# VALVEBOARD_Controller.net
KiCad netlist of a schematic drawn in Altium Designer
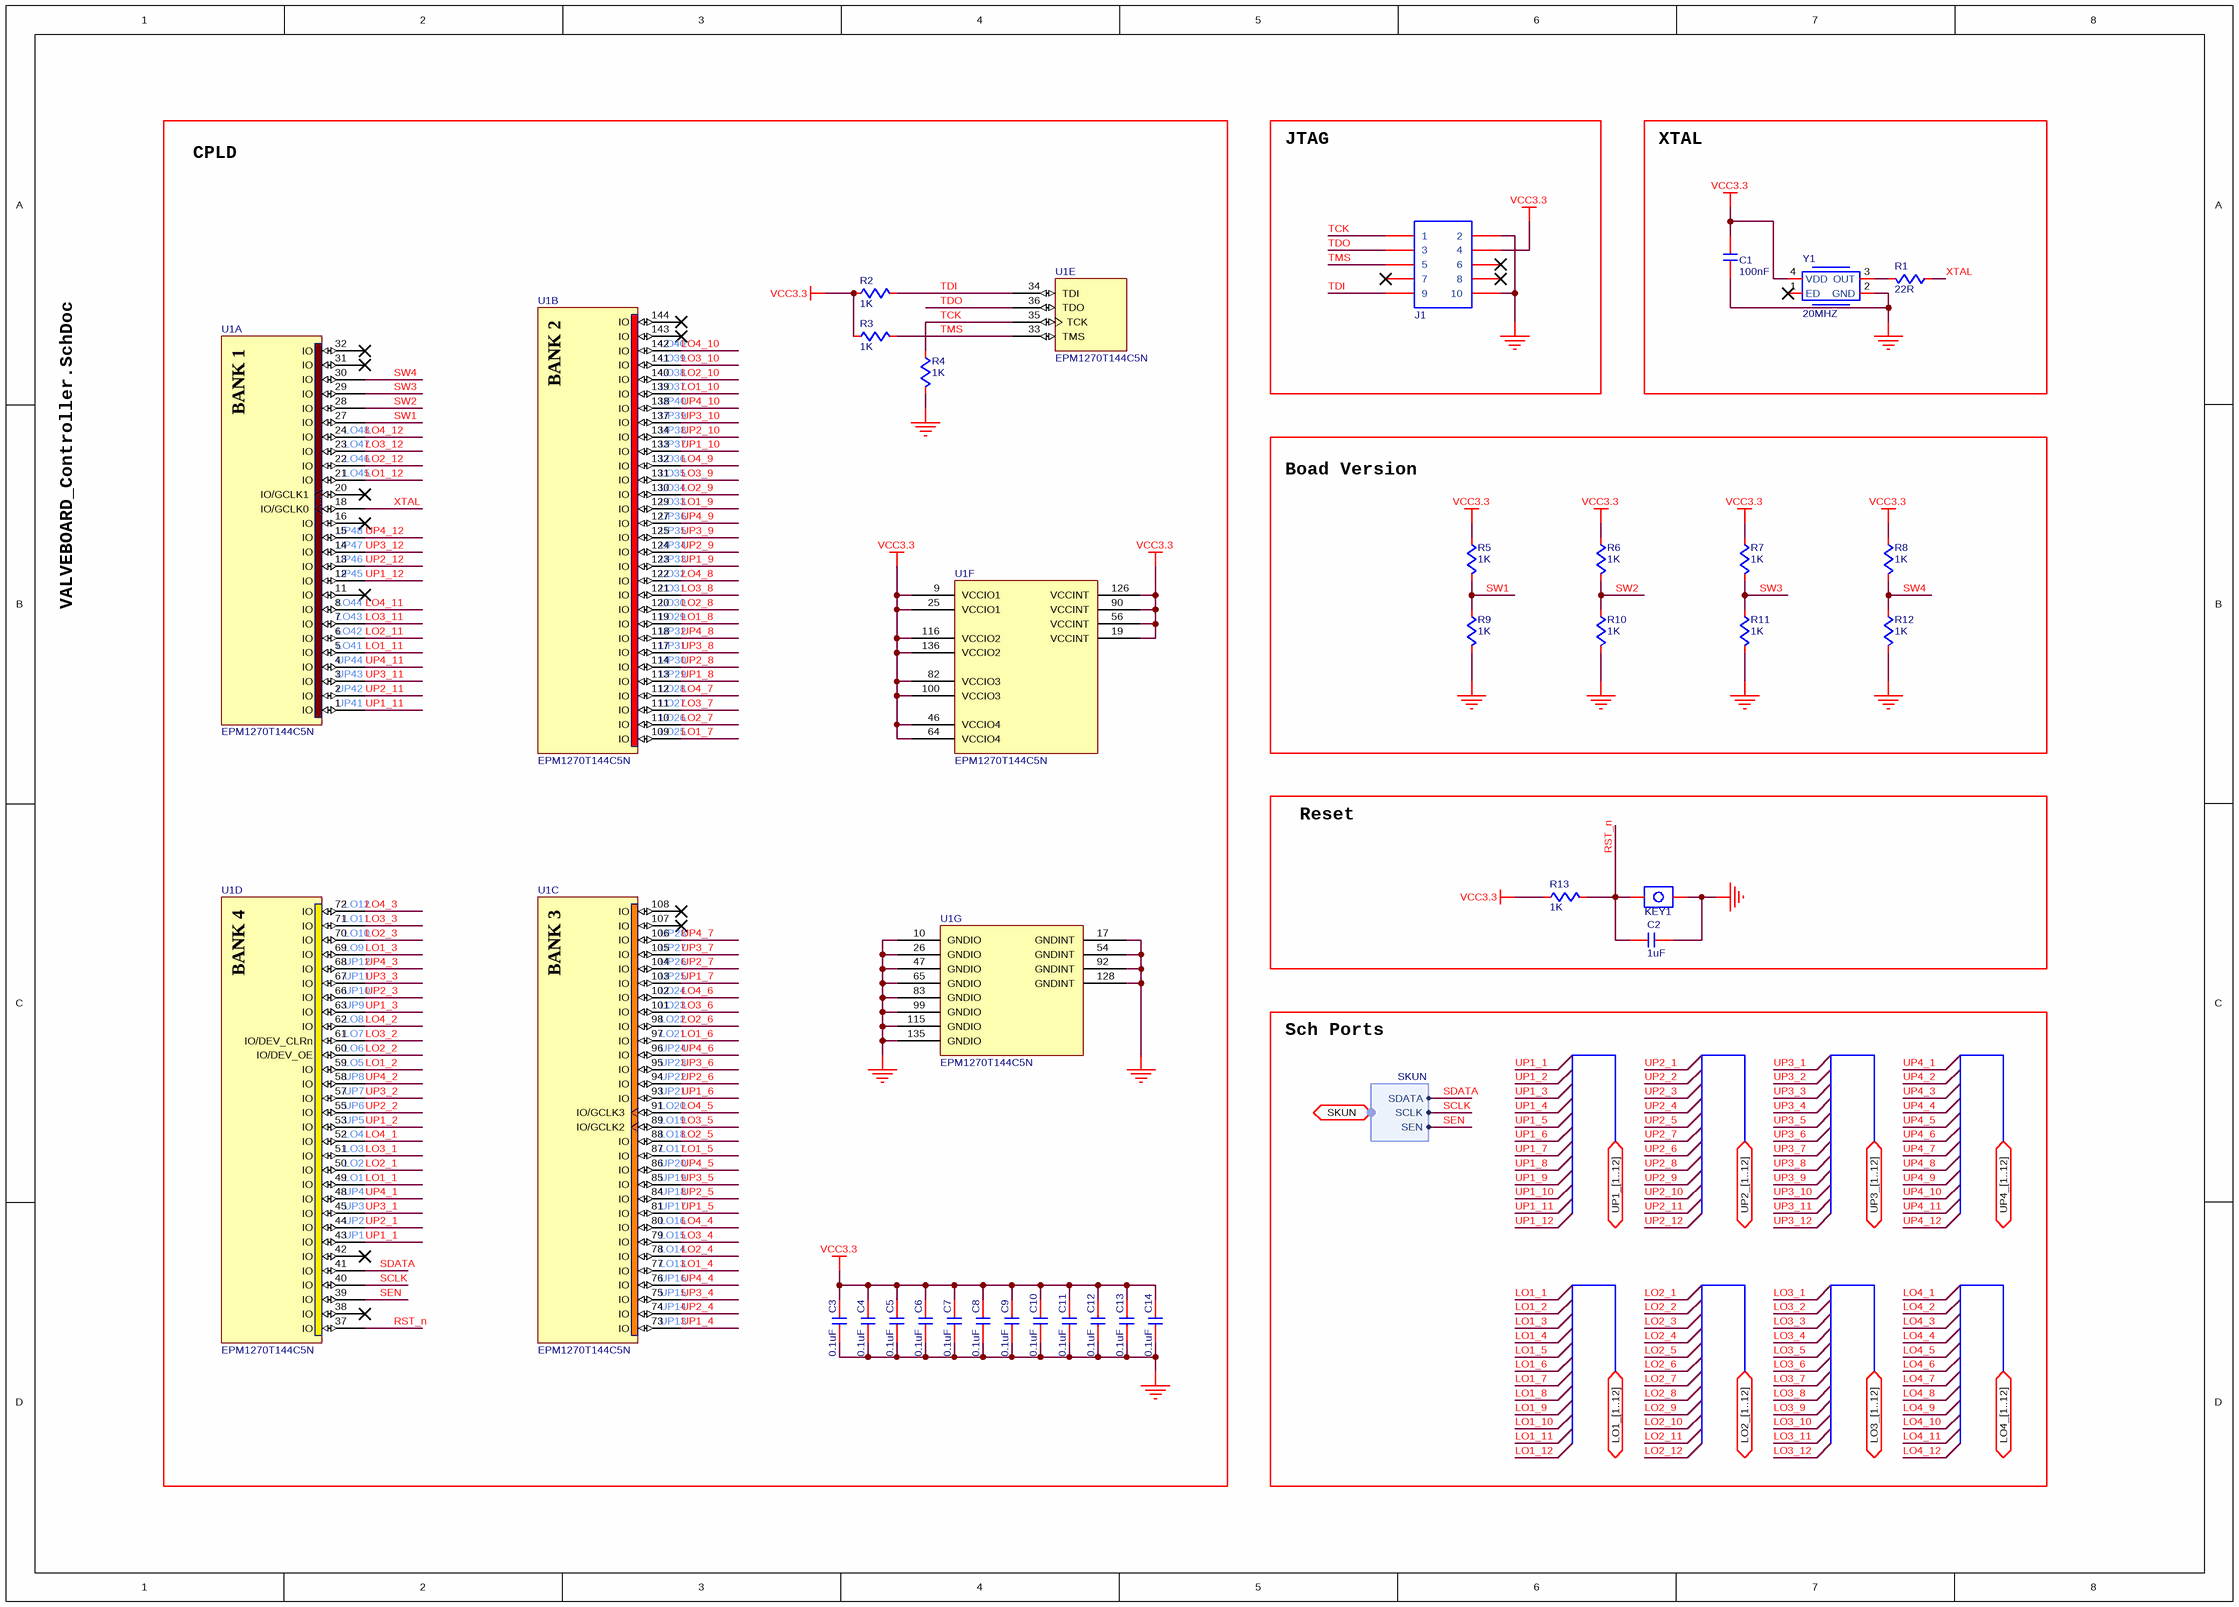
[diagram p0: VALVEBOARD_Controller.SchDoc]

(export (version "E")
  (design (tool "Eeschema 10.0.6"))
  (components
    (comp (ref "C1")
      (value "100nF")
      (footprint "zynq:C0402")
      (fields (field (name "VOLTAGE") "25V") (field (name "Comment") "C-NOMO"))
      (libsource (lib "zynq") (part "C-NOMO"))
    )
    (comp (ref "C2")
      (value "1uF")
      (footprint "zynq:C0402")
      (fields (field (name "VOLTAGE") "25V") (field (name "Comment") "C-NOMO"))
      (libsource (lib "zynq") (part "C-NOMO"))
    )
    (comp (ref "C3")
      (value "0.1uF")
      (footprint "zynq:C0402")
      (fields (field (name "VOLTAGE") "25V") (field (name "Comment") "C-NOMO"))
      (libsource (lib "zynq") (part "C-NOMO"))
    )
    (comp (ref "C4")
      (value "0.1uF")
      (footprint "zynq:C0402")
      (fields (field (name "VOLTAGE") "25V") (field (name "Comment") "C-NOMO"))
      (libsource (lib "zynq") (part "C-NOMO"))
    )
    (comp (ref "C5")
      (value "0.1uF")
      (footprint "zynq:C0402")
      (fields (field (name "VOLTAGE") "25V") (field (name "Comment") "C-NOMO"))
      (libsource (lib "zynq") (part "C-NOMO"))
    )
    (comp (ref "C6")
      (value "0.1uF")
      (footprint "zynq:C0402")
      (fields (field (name "VOLTAGE") "25V") (field (name "Comment") "C-NOMO"))
      (libsource (lib "zynq") (part "C-NOMO"))
    )
    (comp (ref "C7")
      (value "0.1uF")
      (footprint "zynq:C0402")
      (fields (field (name "VOLTAGE") "25V") (field (name "Comment") "C-NOMO"))
      (libsource (lib "zynq") (part "C-NOMO"))
    )
    (comp (ref "C8")
      (value "0.1uF")
      (footprint "zynq:C0402")
      (fields (field (name "VOLTAGE") "25V") (field (name "Comment") "C-NOMO"))
      (libsource (lib "zynq") (part "C-NOMO"))
    )
    (comp (ref "C9")
      (value "0.1uF")
      (footprint "zynq:C0402")
      (fields (field (name "VOLTAGE") "25V") (field (name "Comment") "C-NOMO"))
      (libsource (lib "zynq") (part "C-NOMO"))
    )
    (comp (ref "C10")
      (value "0.1uF")
      (footprint "zynq:C0402")
      (fields (field (name "VOLTAGE") "25V") (field (name "Comment") "C-NOMO"))
      (libsource (lib "zynq") (part "C-NOMO"))
    )
    (comp (ref "C11")
      (value "0.1uF")
      (footprint "zynq:C0402")
      (fields (field (name "VOLTAGE") "25V") (field (name "Comment") "C-NOMO"))
      (libsource (lib "zynq") (part "C-NOMO"))
    )
    (comp (ref "C12")
      (value "0.1uF")
      (footprint "zynq:C0402")
      (fields (field (name "VOLTAGE") "25V") (field (name "Comment") "C-NOMO"))
      (libsource (lib "zynq") (part "C-NOMO"))
    )
    (comp (ref "C13")
      (value "0.1uF")
      (footprint "zynq:C0402")
      (fields (field (name "VOLTAGE") "25V") (field (name "Comment") "C-NOMO"))
      (libsource (lib "zynq") (part "C-NOMO"))
    )
    (comp (ref "C14")
      (value "0.1uF")
      (footprint "zynq:C0402")
      (fields (field (name "VOLTAGE") "25V") (field (name "Comment") "C-NOMO"))
      (libsource (lib "zynq") (part "C-NOMO"))
    )
    (comp (ref "J1") (value "HDR2X5") (footprint "zynq:HDR2X5-NJ") (libsource (lib "zynq") (part "HDR2X5")))
    (comp (ref "KEY1") (value "KEY") (footprint "zynq:KEY735SO") (libsource (lib "zynq") (part "KEY")))
    (comp (ref "R1")
      (value "22R")
      (footprint "zynq:R0402")
      (fields (field (name "Comment") "R"))
      (libsource (lib "zynq") (part "R"))
    )
    (comp (ref "R2")
      (value "1K")
      (footprint "zynq:R0402")
      (fields (field (name "Comment") "R"))
      (libsource (lib "zynq") (part "R"))
    )
    (comp (ref "R3")
      (value "1K")
      (footprint "zynq:R0402")
      (fields (field (name "Comment") "R"))
      (libsource (lib "zynq") (part "R"))
    )
    (comp (ref "R4")
      (value "1K")
      (footprint "zynq:R0402")
      (fields (field (name "Comment") "R"))
      (libsource (lib "zynq") (part "R"))
    )
    (comp (ref "R5")
      (value "1K")
      (footprint "zynq:R0402")
      (fields (field (name "Comment") "R"))
      (libsource (lib "zynq") (part "R"))
    )
    (comp (ref "R6")
      (value "1K")
      (footprint "zynq:R0402")
      (fields (field (name "Comment") "R"))
      (libsource (lib "zynq") (part "R"))
    )
    (comp (ref "R7")
      (value "1K")
      (footprint "zynq:R0402")
      (fields (field (name "Comment") "R"))
      (libsource (lib "zynq") (part "R"))
    )
    (comp (ref "R8")
      (value "1K")
      (footprint "zynq:R0402")
      (fields (field (name "Comment") "R"))
      (libsource (lib "zynq") (part "R"))
    )
    (comp (ref "R9")
      (value "1K")
      (footprint "zynq:R0402")
      (fields (field (name "Comment") "R"))
      (libsource (lib "zynq") (part "R"))
    )
    (comp (ref "R10")
      (value "1K")
      (footprint "zynq:R0402")
      (fields (field (name "Comment") "R"))
      (libsource (lib "zynq") (part "R"))
    )
    (comp (ref "R11")
      (value "1K")
      (footprint "zynq:R0402")
      (fields (field (name "Comment") "R"))
      (libsource (lib "zynq") (part "R"))
    )
    (comp (ref "R12")
      (value "1K")
      (footprint "zynq:R0402")
      (fields (field (name "Comment") "R"))
      (libsource (lib "zynq") (part "R"))
    )
    (comp (ref "R13")
      (value "1K")
      (footprint "zynq:R0402")
      (fields (field (name "Comment") "R"))
      (libsource (lib "zynq") (part "R"))
    )
    (comp (ref "U1")
      (value "EPM1270T144C5N")
      (footprint "TQFP144_N")
      (libsource (lib "MAX II") (part "EPM1270T144C5N"))
    )
    (comp (ref "Y1")
      (value "XTAL")
      (footprint "zynq:OSC3225")
      (fields (field (name "FREQUENCY") "20MHZ"))
      (libsource (lib "zynq") (part "XTAL"))
    )
  )
  (nets
    (net (code "2") (name "/LO1_1") (class "Default")
      (node (ref "U1") (pin "49") (pinfunction "IO_49") (pintype "bidirectional"))
    )
    (net (code "3") (name "/LO1_2") (class "Default")
      (node (ref "U1") (pin "59") (pinfunction "IO_59") (pintype "bidirectional"))
    )
    (net (code "4") (name "/LO1_3") (class "Default")
      (node (ref "U1") (pin "69") (pinfunction "IO_69") (pintype "bidirectional"))
    )
    (net (code "5") (name "/LO1_4") (class "Default")
      (node (ref "U1") (pin "77") (pinfunction "IO_77") (pintype "bidirectional"))
    )
    (net (code "6") (name "/LO1_5") (class "Default")
      (node (ref "U1") (pin "87") (pinfunction "IO_87") (pintype "bidirectional"))
    )
    (net (code "7") (name "/LO1_6") (class "Default")
      (node (ref "U1") (pin "97") (pinfunction "IO_97") (pintype "bidirectional"))
    )
    (net (code "8") (name "/LO1_7") (class "Default")
      (node (ref "U1") (pin "109") (pinfunction "IO_109") (pintype "bidirectional"))
    )
    (net (code "9") (name "/LO1_8") (class "Default")
      (node (ref "U1") (pin "119") (pinfunction "IO_119") (pintype "bidirectional"))
    )
    (net (code "10") (name "/LO1_9") (class "Default")
      (node (ref "U1") (pin "129") (pinfunction "IO_129") (pintype "bidirectional"))
    )
    (net (code "11") (name "/LO1_10") (class "Default")
      (node (ref "U1") (pin "139") (pinfunction "IO_139") (pintype "bidirectional"))
    )
    (net (code "12") (name "/LO1_11") (class "Default")
      (node (ref "U1") (pin "5") (pinfunction "IO_5") (pintype "bidirectional"))
    )
    (net (code "13") (name "/LO1_12") (class "Default")
      (node (ref "U1") (pin "21") (pinfunction "IO_21") (pintype "bidirectional"))
    )
    (net (code "15") (name "/LO2_1") (class "Default")
      (node (ref "U1") (pin "50") (pinfunction "IO_50") (pintype "bidirectional"))
    )
    (net (code "16") (name "/LO2_2") (class "Default")
      (node (ref "U1") (pin "60") (pinfunction "IO/DEV_OE_60") (pintype "bidirectional"))
    )
    (net (code "17") (name "/LO2_3") (class "Default")
      (node (ref "U1") (pin "70") (pinfunction "IO_70") (pintype "bidirectional"))
    )
    (net (code "18") (name "/LO2_4") (class "Default")
      (node (ref "U1") (pin "78") (pinfunction "IO_78") (pintype "bidirectional"))
    )
    (net (code "19") (name "/LO2_5") (class "Default")
      (node (ref "U1") (pin "88") (pinfunction "IO_88") (pintype "bidirectional"))
    )
    (net (code "20") (name "/LO2_6") (class "Default")
      (node (ref "U1") (pin "98") (pinfunction "IO_98") (pintype "bidirectional"))
    )
    (net (code "21") (name "/LO2_7") (class "Default")
      (node (ref "U1") (pin "110") (pinfunction "IO_110") (pintype "bidirectional"))
    )
    (net (code "22") (name "/LO2_8") (class "Default")
      (node (ref "U1") (pin "120") (pinfunction "IO_120") (pintype "bidirectional"))
    )
    (net (code "23") (name "/LO2_9") (class "Default")
      (node (ref "U1") (pin "130") (pinfunction "IO_130") (pintype "bidirectional"))
    )
    (net (code "24") (name "/LO2_10") (class "Default")
      (node (ref "U1") (pin "140") (pinfunction "IO_140") (pintype "bidirectional"))
    )
    (net (code "25") (name "/LO2_11") (class "Default")
      (node (ref "U1") (pin "6") (pinfunction "IO_6") (pintype "bidirectional"))
    )
    (net (code "26") (name "/LO2_12") (class "Default")
      (node (ref "U1") (pin "22") (pinfunction "IO_22") (pintype "bidirectional"))
    )
    (net (code "28") (name "/LO3_1") (class "Default")
      (node (ref "U1") (pin "51") (pinfunction "IO_51") (pintype "bidirectional"))
    )
    (net (code "29") (name "/LO3_2") (class "Default")
      (node (ref "U1") (pin "61") (pinfunction "IO/DEV_CLRn_61") (pintype "bidirectional"))
    )
    (net (code "30") (name "/LO3_3") (class "Default")
      (node (ref "U1") (pin "71") (pinfunction "IO_71") (pintype "bidirectional"))
    )
    (net (code "31") (name "/LO3_4") (class "Default")
      (node (ref "U1") (pin "79") (pinfunction "IO_79") (pintype "bidirectional"))
    )
    (net (code "32") (name "/LO3_5") (class "Default")
      (node (ref "U1") (pin "89") (pinfunction "IO/GCLK2_89") (pintype "bidirectional"))
    )
    (net (code "33") (name "/LO3_6") (class "Default")
      (node (ref "U1") (pin "101") (pinfunction "IO_101") (pintype "bidirectional"))
    )
    (net (code "34") (name "/LO3_7") (class "Default")
      (node (ref "U1") (pin "111") (pinfunction "IO_111") (pintype "bidirectional"))
    )
    (net (code "35") (name "/LO3_8") (class "Default")
      (node (ref "U1") (pin "121") (pinfunction "IO_121") (pintype "bidirectional"))
    )
    (net (code "36") (name "/LO3_9") (class "Default")
      (node (ref "U1") (pin "131") (pinfunction "IO_131") (pintype "bidirectional"))
    )
    (net (code "37") (name "/LO3_10") (class "Default")
      (node (ref "U1") (pin "141") (pinfunction "IO_141") (pintype "bidirectional"))
    )
    (net (code "38") (name "/LO3_11") (class "Default")
      (node (ref "U1") (pin "7") (pinfunction "IO_7") (pintype "bidirectional"))
    )
    (net (code "39") (name "/LO3_12") (class "Default")
      (node (ref "U1") (pin "23") (pinfunction "IO_23") (pintype "bidirectional"))
    )
    (net (code "41") (name "/LO4_1") (class "Default")
      (node (ref "U1") (pin "52") (pinfunction "IO_52") (pintype "bidirectional"))
    )
    (net (code "42") (name "/LO4_2") (class "Default")
      (node (ref "U1") (pin "62") (pinfunction "IO_62") (pintype "bidirectional"))
    )
    (net (code "43") (name "/LO4_3") (class "Default")
      (node (ref "U1") (pin "72") (pinfunction "IO_72") (pintype "bidirectional"))
    )
    (net (code "44") (name "/LO4_4") (class "Default")
      (node (ref "U1") (pin "80") (pinfunction "IO_80") (pintype "bidirectional"))
    )
    (net (code "45") (name "/LO4_5") (class "Default")
      (node (ref "U1") (pin "91") (pinfunction "IO/GCLK3_91") (pintype "bidirectional"))
    )
    (net (code "46") (name "/LO4_6") (class "Default")
      (node (ref "U1") (pin "102") (pinfunction "IO_102") (pintype "bidirectional"))
    )
    (net (code "47") (name "/LO4_7") (class "Default")
      (node (ref "U1") (pin "112") (pinfunction "IO_112") (pintype "bidirectional"))
    )
    (net (code "48") (name "/LO4_8") (class "Default")
      (node (ref "U1") (pin "122") (pinfunction "IO_122") (pintype "bidirectional"))
    )
    (net (code "49") (name "/LO4_9") (class "Default")
      (node (ref "U1") (pin "132") (pinfunction "IO_132") (pintype "bidirectional"))
    )
    (net (code "50") (name "/LO4_10") (class "Default")
      (node (ref "U1") (pin "142") (pinfunction "IO_142") (pintype "bidirectional"))
    )
    (net (code "51") (name "/LO4_11") (class "Default")
      (node (ref "U1") (pin "8") (pinfunction "IO_8") (pintype "bidirectional"))
    )
    (net (code "52") (name "/LO4_12") (class "Default")
      (node (ref "U1") (pin "24") (pinfunction "IO_24") (pintype "bidirectional"))
    )
    (net (code "54") (name "/RST_n") (class "Default")
      (node (ref "C2") (pin "2") (pinfunction "2_2") (pintype "passive"))
      (node (ref "KEY1") (pin "2") (pinfunction "2_2") (pintype "passive"))
      (node (ref "R13") (pin "1") (pinfunction "1_1") (pintype "passive"))
      (node (ref "U1") (pin "37") (pinfunction "IO_37") (pintype "bidirectional"))
    )
    (net (code "55") (name "/SCLK") (class "Default")
      (node (ref "U1") (pin "40") (pinfunction "IO_40") (pintype "bidirectional"))
    )
    (net (code "56") (name "/SDATA") (class "Default")
      (node (ref "U1") (pin "41") (pinfunction "IO_41") (pintype "bidirectional"))
    )
    (net (code "57") (name "/SEN") (class "Default")
      (node (ref "U1") (pin "39") (pinfunction "IO_39") (pintype "bidirectional"))
    )
    (net (code "58") (name "/SW1") (class "Default")
      (node (ref "R5") (pin "1") (pinfunction "1_1") (pintype "passive"))
      (node (ref "R9") (pin "2") (pinfunction "2_2") (pintype "passive"))
      (node (ref "U1") (pin "27") (pinfunction "IO_27") (pintype "bidirectional"))
    )
    (net (code "59") (name "/SW2") (class "Default")
      (node (ref "R10") (pin "2") (pinfunction "2_2") (pintype "passive"))
      (node (ref "R6") (pin "1") (pinfunction "1_1") (pintype "passive"))
      (node (ref "U1") (pin "28") (pinfunction "IO_28") (pintype "bidirectional"))
    )
    (net (code "60") (name "/SW3") (class "Default")
      (node (ref "R11") (pin "2") (pinfunction "2_2") (pintype "passive"))
      (node (ref "R7") (pin "1") (pinfunction "1_1") (pintype "passive"))
      (node (ref "U1") (pin "29") (pinfunction "IO_29") (pintype "bidirectional"))
    )
    (net (code "61") (name "/SW4") (class "Default")
      (node (ref "R12") (pin "2") (pinfunction "2_2") (pintype "passive"))
      (node (ref "R8") (pin "1") (pinfunction "1_1") (pintype "passive"))
      (node (ref "U1") (pin "30") (pinfunction "IO_30") (pintype "bidirectional"))
    )
    (net (code "62") (name "/TCK") (class "Default")
      (node (ref "J1") (pin "1") (pinfunction "1_1") (pintype "passive"))
      (node (ref "R4") (pin "2") (pinfunction "2_2") (pintype "passive"))
      (node (ref "U1") (pin "35") (pinfunction "TCK_35") (pintype "bidirectional"))
    )
    (net (code "63") (name "/TDI") (class "Default")
      (node (ref "J1") (pin "9") (pinfunction "9_9") (pintype "passive"))
      (node (ref "R2") (pin "1") (pinfunction "1_1") (pintype "passive"))
      (node (ref "U1") (pin "34") (pinfunction "TDI_34") (pintype "bidirectional"))
    )
    (net (code "64") (name "/TDO") (class "Default")
      (node (ref "J1") (pin "3") (pinfunction "3_3") (pintype "passive"))
      (node (ref "U1") (pin "36") (pinfunction "TDO_36") (pintype "bidirectional"))
    )
    (net (code "65") (name "/TMS") (class "Default")
      (node (ref "J1") (pin "5") (pinfunction "5_5") (pintype "passive"))
      (node (ref "R3") (pin "1") (pinfunction "1_1") (pintype "passive"))
      (node (ref "U1") (pin "33") (pinfunction "TMS_33") (pintype "bidirectional"))
    )
    (net (code "66") (name "/UP1_1") (class "Default")
      (node (ref "U1") (pin "43") (pinfunction "IO_43") (pintype "bidirectional"))
    )
    (net (code "67") (name "/UP1_2") (class "Default")
      (node (ref "U1") (pin "53") (pinfunction "IO_53") (pintype "bidirectional"))
    )
    (net (code "68") (name "/UP1_3") (class "Default")
      (node (ref "U1") (pin "63") (pinfunction "IO_63") (pintype "bidirectional"))
    )
    (net (code "69") (name "/UP1_4") (class "Default")
      (node (ref "U1") (pin "73") (pinfunction "IO_73") (pintype "bidirectional"))
    )
    (net (code "70") (name "/UP1_5") (class "Default")
      (node (ref "U1") (pin "81") (pinfunction "IO_81") (pintype "bidirectional"))
    )
    (net (code "71") (name "/UP1_6") (class "Default")
      (node (ref "U1") (pin "93") (pinfunction "IO_93") (pintype "bidirectional"))
    )
    (net (code "72") (name "/UP1_7") (class "Default")
      (node (ref "U1") (pin "103") (pinfunction "IO_103") (pintype "bidirectional"))
    )
    (net (code "73") (name "/UP1_8") (class "Default")
      (node (ref "U1") (pin "113") (pinfunction "IO_113") (pintype "bidirectional"))
    )
    (net (code "74") (name "/UP1_9") (class "Default")
      (node (ref "U1") (pin "123") (pinfunction "IO_123") (pintype "bidirectional"))
    )
    (net (code "75") (name "/UP1_10") (class "Default")
      (node (ref "U1") (pin "133") (pinfunction "IO_133") (pintype "bidirectional"))
    )
    (net (code "76") (name "/UP1_11") (class "Default")
      (node (ref "U1") (pin "1") (pinfunction "IO_1") (pintype "bidirectional"))
    )
    (net (code "77") (name "/UP1_12") (class "Default")
      (node (ref "U1") (pin "12") (pinfunction "IO_12") (pintype "bidirectional"))
    )
    (net (code "79") (name "/UP2_1") (class "Default")
      (node (ref "U1") (pin "44") (pinfunction "IO_44") (pintype "bidirectional"))
    )
    (net (code "80") (name "/UP2_2") (class "Default")
      (node (ref "U1") (pin "55") (pinfunction "IO_55") (pintype "bidirectional"))
    )
    (net (code "81") (name "/UP2_3") (class "Default")
      (node (ref "U1") (pin "66") (pinfunction "IO_66") (pintype "bidirectional"))
    )
    (net (code "82") (name "/UP2_4") (class "Default")
      (node (ref "U1") (pin "74") (pinfunction "IO_74") (pintype "bidirectional"))
    )
    (net (code "83") (name "/UP2_5") (class "Default")
      (node (ref "U1") (pin "84") (pinfunction "IO_84") (pintype "bidirectional"))
    )
    (net (code "84") (name "/UP2_6") (class "Default")
      (node (ref "U1") (pin "94") (pinfunction "IO_94") (pintype "bidirectional"))
    )
    (net (code "85") (name "/UP2_7") (class "Default")
      (node (ref "U1") (pin "104") (pinfunction "IO_104") (pintype "bidirectional"))
    )
    (net (code "86") (name "/UP2_8") (class "Default")
      (node (ref "U1") (pin "114") (pinfunction "IO_114") (pintype "bidirectional"))
    )
    (net (code "87") (name "/UP2_9") (class "Default")
      (node (ref "U1") (pin "124") (pinfunction "IO_124") (pintype "bidirectional"))
    )
    (net (code "88") (name "/UP2_10") (class "Default")
      (node (ref "U1") (pin "134") (pinfunction "IO_134") (pintype "bidirectional"))
    )
    (net (code "89") (name "/UP2_11") (class "Default")
      (node (ref "U1") (pin "2") (pinfunction "IO_2") (pintype "bidirectional"))
    )
    (net (code "90") (name "/UP2_12") (class "Default")
      (node (ref "U1") (pin "13") (pinfunction "IO_13") (pintype "bidirectional"))
    )
    (net (code "92") (name "/UP3_1") (class "Default")
      (node (ref "U1") (pin "45") (pinfunction "IO_45") (pintype "bidirectional"))
    )
    (net (code "93") (name "/UP3_2") (class "Default")
      (node (ref "U1") (pin "57") (pinfunction "IO_57") (pintype "bidirectional"))
    )
    (net (code "94") (name "/UP3_3") (class "Default")
      (node (ref "U1") (pin "67") (pinfunction "IO_67") (pintype "bidirectional"))
    )
    (net (code "95") (name "/UP3_4") (class "Default")
      (node (ref "U1") (pin "75") (pinfunction "IO_75") (pintype "bidirectional"))
    )
    (net (code "96") (name "/UP3_5") (class "Default")
      (node (ref "U1") (pin "85") (pinfunction "IO_85") (pintype "bidirectional"))
    )
    (net (code "97") (name "/UP3_6") (class "Default")
      (node (ref "U1") (pin "95") (pinfunction "IO_95") (pintype "bidirectional"))
    )
    (net (code "98") (name "/UP3_7") (class "Default")
      (node (ref "U1") (pin "105") (pinfunction "IO_105") (pintype "bidirectional"))
    )
    (net (code "99") (name "/UP3_8") (class "Default")
      (node (ref "U1") (pin "117") (pinfunction "IO_117") (pintype "bidirectional"))
    )
    (net (code "100") (name "/UP3_9") (class "Default")
      (node (ref "U1") (pin "125") (pinfunction "IO_125") (pintype "bidirectional"))
    )
    (net (code "101") (name "/UP3_10") (class "Default")
      (node (ref "U1") (pin "137") (pinfunction "IO_137") (pintype "bidirectional"))
    )
    (net (code "102") (name "/UP3_11") (class "Default")
      (node (ref "U1") (pin "3") (pinfunction "IO_3") (pintype "bidirectional"))
    )
    (net (code "103") (name "/UP3_12") (class "Default")
      (node (ref "U1") (pin "14") (pinfunction "IO_14") (pintype "bidirectional"))
    )
    (net (code "105") (name "/UP4_1") (class "Default")
      (node (ref "U1") (pin "48") (pinfunction "IO_48") (pintype "bidirectional"))
    )
    (net (code "106") (name "/UP4_2") (class "Default")
      (node (ref "U1") (pin "58") (pinfunction "IO_58") (pintype "bidirectional"))
    )
    (net (code "107") (name "/UP4_3") (class "Default")
      (node (ref "U1") (pin "68") (pinfunction "IO_68") (pintype "bidirectional"))
    )
    (net (code "108") (name "/UP4_4") (class "Default")
      (node (ref "U1") (pin "76") (pinfunction "IO_76") (pintype "bidirectional"))
    )
    (net (code "109") (name "/UP4_5") (class "Default")
      (node (ref "U1") (pin "86") (pinfunction "IO_86") (pintype "bidirectional"))
    )
    (net (code "110") (name "/UP4_6") (class "Default")
      (node (ref "U1") (pin "96") (pinfunction "IO_96") (pintype "bidirectional"))
    )
    (net (code "111") (name "/UP4_7") (class "Default")
      (node (ref "U1") (pin "106") (pinfunction "IO_106") (pintype "bidirectional"))
    )
    (net (code "112") (name "/UP4_8") (class "Default")
      (node (ref "U1") (pin "118") (pinfunction "IO_118") (pintype "bidirectional"))
    )
    (net (code "113") (name "/UP4_9") (class "Default")
      (node (ref "U1") (pin "127") (pinfunction "IO_127") (pintype "bidirectional"))
    )
    (net (code "114") (name "/UP4_10") (class "Default")
      (node (ref "U1") (pin "138") (pinfunction "IO_138") (pintype "bidirectional"))
    )
    (net (code "115") (name "/UP4_11") (class "Default")
      (node (ref "U1") (pin "4") (pinfunction "IO_4") (pintype "bidirectional"))
    )
    (net (code "116") (name "/UP4_12") (class "Default")
      (node (ref "U1") (pin "15") (pinfunction "IO_15") (pintype "bidirectional"))
    )
    (net (code "118") (name "/XTAL") (class "Default")
      (node (ref "R1") (pin "2") (pinfunction "2_2") (pintype "passive"))
      (node (ref "U1") (pin "18") (pinfunction "IO/GCLK0_18") (pintype "bidirectional"))
    )
    (net (code "120") (name "DGND") (class "Default")
      (node (ref "C1") (pin "1") (pinfunction "1_1") (pintype "passive"))
      (node (ref "C10") (pin "1") (pinfunction "1_1") (pintype "passive"))
      (node (ref "C11") (pin "1") (pinfunction "1_1") (pintype "passive"))
      (node (ref "C12") (pin "1") (pinfunction "1_1") (pintype "passive"))
      (node (ref "C13") (pin "1") (pinfunction "1_1") (pintype "passive"))
      (node (ref "C14") (pin "1") (pinfunction "1_1") (pintype "passive"))
      (node (ref "C2") (pin "1") (pinfunction "1_1") (pintype "passive"))
      (node (ref "C3") (pin "1") (pinfunction "1_1") (pintype "passive"))
      (node (ref "C4") (pin "1") (pinfunction "1_1") (pintype "passive"))
      (node (ref "C5") (pin "1") (pinfunction "1_1") (pintype "passive"))
      (node (ref "C6") (pin "1") (pinfunction "1_1") (pintype "passive"))
      (node (ref "C7") (pin "1") (pinfunction "1_1") (pintype "passive"))
      (node (ref "C8") (pin "1") (pinfunction "1_1") (pintype "passive"))
      (node (ref "C9") (pin "1") (pinfunction "1_1") (pintype "passive"))
      (node (ref "J1") (pin "10") (pinfunction "10_10") (pintype "passive"))
      (node (ref "J1") (pin "2") (pinfunction "2_2") (pintype "passive"))
      (node (ref "KEY1") (pin "1") (pinfunction "1_1") (pintype "passive"))
      (node (ref "R10") (pin "1") (pinfunction "1_1") (pintype "passive"))
      (node (ref "R11") (pin "1") (pinfunction "1_1") (pintype "passive"))
      (node (ref "R12") (pin "1") (pinfunction "1_1") (pintype "passive"))
      (node (ref "R4") (pin "1") (pinfunction "1_1") (pintype "passive"))
      (node (ref "R9") (pin "1") (pinfunction "1_1") (pintype "passive"))
      (node (ref "U1") (pin "10") (pinfunction "GNDIO_10") (pintype "power_in"))
      (node (ref "U1") (pin "115") (pinfunction "GNDIO_115") (pintype "power_in"))
      (node (ref "U1") (pin "128") (pinfunction "GNDINT_128") (pintype "power_in"))
      (node (ref "U1") (pin "135") (pinfunction "GNDIO_135") (pintype "power_in"))
      (node (ref "U1") (pin "17") (pinfunction "GNDINT_17") (pintype "power_in"))
      (node (ref "U1") (pin "26") (pinfunction "GNDIO_26") (pintype "power_in"))
      (node (ref "U1") (pin "47") (pinfunction "GNDIO_47") (pintype "power_in"))
      (node (ref "U1") (pin "54") (pinfunction "GNDINT_54") (pintype "power_in"))
      (node (ref "U1") (pin "65") (pinfunction "GNDIO_65") (pintype "power_in"))
      (node (ref "U1") (pin "83") (pinfunction "GNDIO_83") (pintype "power_in"))
      (node (ref "U1") (pin "92") (pinfunction "GNDINT_92") (pintype "power_in"))
      (node (ref "U1") (pin "99") (pinfunction "GNDIO_99") (pintype "power_in"))
      (node (ref "Y1") (pin "2") (pinfunction "GND_2") (pintype "passive"))
    )
    (net (code "121") (name "Net-(Y1-OUT)") (class "Default")
      (node (ref "R1") (pin "1") (pinfunction "1_1") (pintype "passive"))
      (node (ref "Y1") (pin "3") (pinfunction "OUT_3") (pintype "passive"))
    )
    (net (code "122") (name "VCC3.3") (class "Default")
      (node (ref "C1") (pin "2") (pinfunction "2_2") (pintype "passive"))
      (node (ref "C10") (pin "2") (pinfunction "2_2") (pintype "passive"))
      (node (ref "C11") (pin "2") (pinfunction "2_2") (pintype "passive"))
      (node (ref "C12") (pin "2") (pinfunction "2_2") (pintype "passive"))
      (node (ref "C13") (pin "2") (pinfunction "2_2") (pintype "passive"))
      (node (ref "C14") (pin "2") (pinfunction "2_2") (pintype "passive"))
      (node (ref "C3") (pin "2") (pinfunction "2_2") (pintype "passive"))
      (node (ref "C4") (pin "2") (pinfunction "2_2") (pintype "passive"))
      (node (ref "C5") (pin "2") (pinfunction "2_2") (pintype "passive"))
      (node (ref "C6") (pin "2") (pinfunction "2_2") (pintype "passive"))
      (node (ref "C7") (pin "2") (pinfunction "2_2") (pintype "passive"))
      (node (ref "C8") (pin "2") (pinfunction "2_2") (pintype "passive"))
      (node (ref "C9") (pin "2") (pinfunction "2_2") (pintype "passive"))
      (node (ref "J1") (pin "4") (pinfunction "4_4") (pintype "passive"))
      (node (ref "R13") (pin "2") (pinfunction "2_2") (pintype "passive"))
      (node (ref "R2") (pin "2") (pinfunction "2_2") (pintype "passive"))
      (node (ref "R3") (pin "2") (pinfunction "2_2") (pintype "passive"))
      (node (ref "R5") (pin "2") (pinfunction "2_2") (pintype "passive"))
      (node (ref "R6") (pin "2") (pinfunction "2_2") (pintype "passive"))
      (node (ref "R7") (pin "2") (pinfunction "2_2") (pintype "passive"))
      (node (ref "R8") (pin "2") (pinfunction "2_2") (pintype "passive"))
      (node (ref "U1") (pin "100") (pinfunction "VCCIO3_100") (pintype "power_in"))
      (node (ref "U1") (pin "116") (pinfunction "VCCIO2_116") (pintype "power_in"))
      (node (ref "U1") (pin "126") (pinfunction "VCCINT_126") (pintype "power_in"))
      (node (ref "U1") (pin "136") (pinfunction "VCCIO2_136") (pintype "power_in"))
      (node (ref "U1") (pin "19") (pinfunction "VCCINT_19") (pintype "power_in"))
      (node (ref "U1") (pin "25") (pinfunction "VCCIO1_25") (pintype "power_in"))
      (node (ref "U1") (pin "46") (pinfunction "VCCIO4_46") (pintype "power_in"))
      (node (ref "U1") (pin "56") (pinfunction "VCCINT_56") (pintype "power_in"))
      (node (ref "U1") (pin "64") (pinfunction "VCCIO4_64") (pintype "power_in"))
      (node (ref "U1") (pin "82") (pinfunction "VCCIO3_82") (pintype "power_in"))
      (node (ref "U1") (pin "9") (pinfunction "VCCIO1_9") (pintype "power_in"))
      (node (ref "U1") (pin "90") (pinfunction "VCCINT_90") (pintype "power_in"))
      (node (ref "Y1") (pin "4") (pinfunction "VDD_4") (pintype "passive"))
    )
    (net (code "123") (name "unconnected-(J1-Pad6)") (class "Default")
      (node (ref "J1") (pin "6") (pinfunction "6_6") (pintype "passive+no_connect"))
    )
    (net (code "124") (name "unconnected-(J1-Pad7)") (class "Default")
      (node (ref "J1") (pin "7") (pinfunction "7_7") (pintype "passive+no_connect"))
    )
    (net (code "125") (name "unconnected-(J1-Pad8)") (class "Default")
      (node (ref "J1") (pin "8") (pinfunction "8_8") (pintype "passive+no_connect"))
    )
    (net (code "126") (name "unconnected-(U1A-IO-Pad11)") (class "Default")
      (node (ref "U1") (pin "11") (pinfunction "IO_11") (pintype "bidirectional+no_connect"))
    )
    (net (code "127") (name "unconnected-(U1A-IO-Pad16)") (class "Default")
      (node (ref "U1") (pin "16") (pinfunction "IO_16") (pintype "bidirectional+no_connect"))
    )
    (net (code "128") (name "unconnected-(U1A-IO-Pad31)") (class "Default")
      (node (ref "U1") (pin "31") (pinfunction "IO_31") (pintype "bidirectional+no_connect"))
    )
    (net (code "129") (name "unconnected-(U1A-IO-Pad32)") (class "Default")
      (node (ref "U1") (pin "32") (pinfunction "IO_32") (pintype "bidirectional+no_connect"))
    )
    (net (code "130") (name "unconnected-(U1A-IO{slash}GCLK1-Pad20)") (class "Default")
      (node (ref "U1") (pin "20") (pinfunction "IO/GCLK1_20") (pintype "bidirectional+no_connect"))
    )
    (net (code "131") (name "unconnected-(U1B-IO-Pad143)") (class "Default")
      (node (ref "U1") (pin "143") (pinfunction "IO_143") (pintype "bidirectional+no_connect"))
    )
    (net (code "132") (name "unconnected-(U1B-IO-Pad144)") (class "Default")
      (node (ref "U1") (pin "144") (pinfunction "IO_144") (pintype "bidirectional+no_connect"))
    )
    (net (code "133") (name "unconnected-(U1C-IO-Pad107)") (class "Default")
      (node (ref "U1") (pin "107") (pinfunction "IO_107") (pintype "bidirectional+no_connect"))
    )
    (net (code "134") (name "unconnected-(U1C-IO-Pad108)") (class "Default")
      (node (ref "U1") (pin "108") (pinfunction "IO_108") (pintype "bidirectional+no_connect"))
    )
    (net (code "135") (name "unconnected-(U1D-IO-Pad38)") (class "Default")
      (node (ref "U1") (pin "38") (pinfunction "IO_38") (pintype "bidirectional+no_connect"))
    )
    (net (code "136") (name "unconnected-(U1D-IO-Pad42)") (class "Default")
      (node (ref "U1") (pin "42") (pinfunction "IO_42") (pintype "bidirectional+no_connect"))
    )
    (net (code "137") (name "unconnected-(Y1-ED-Pad1)") (class "Default")
      (node (ref "Y1") (pin "1") (pinfunction "ED_1") (pintype "passive+no_connect"))
    )
  )
)
